# Proto_FeatherWing.net
KiCad netlist of a schematic drawn in EAGLE
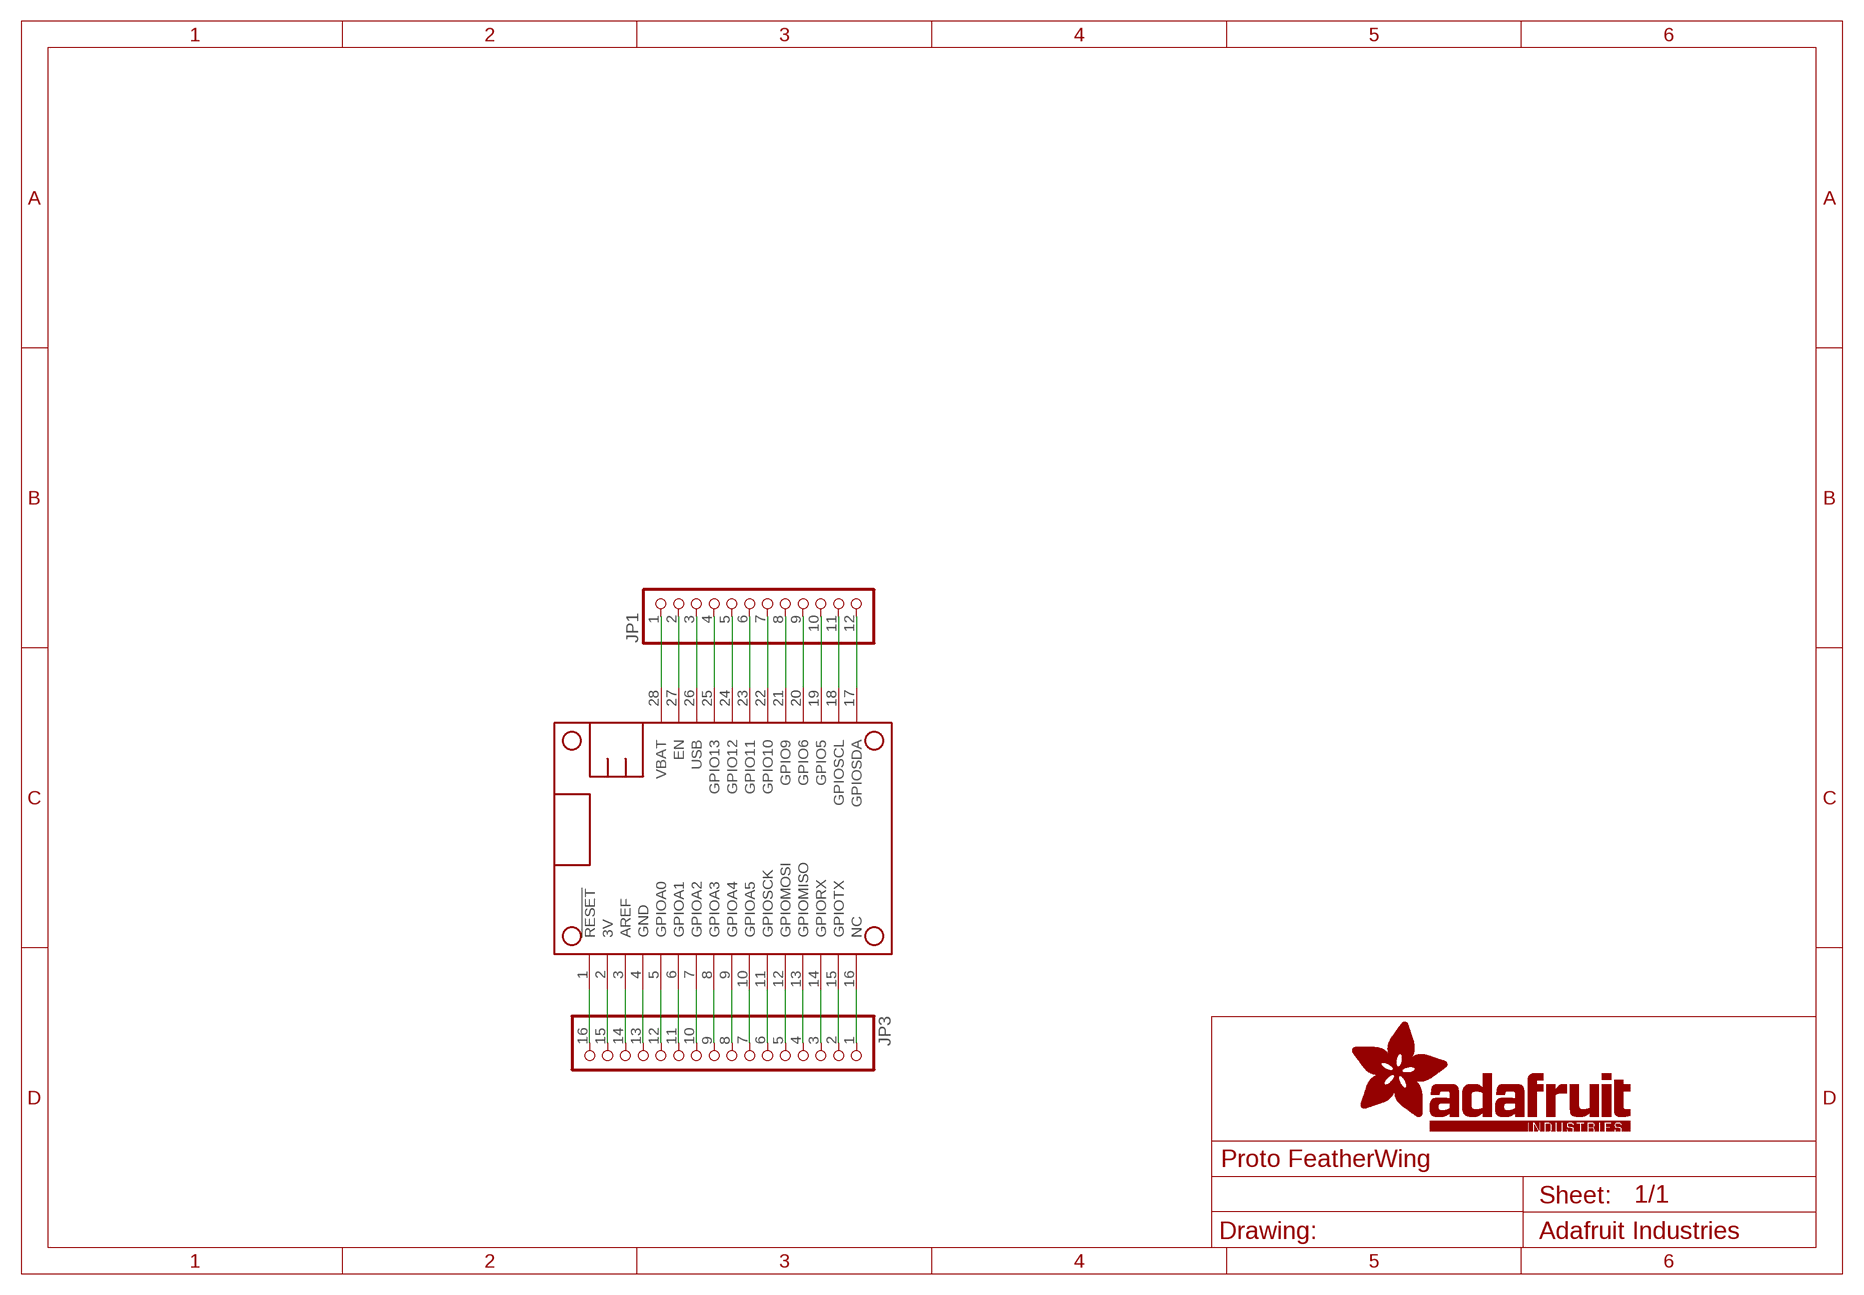
[diagram p0: schematic, sheet 1]

(export (version "E")
  (design (tool "Eeschema 10.0.6"))
  (components
    (comp (ref "JP1")
      (value "HEADER-1X1276MIL")
      (footprint "eagle-import:1X12_ROUND_76MIL")
      (libsource (lib "eagle-import") (part "HEADER-1X1276MIL"))
    )
    (comp (ref "JP3")
      (value "HEADER-1X16_76MIL")
      (footprint "eagle-import:1X16_ROUND_76MIL")
      (libsource (lib "eagle-import") (part "HEADER-1X16_76MIL"))
    )
    (comp (ref "MS1")
      (value "FEATHERWING")
      (footprint "eagle-import:FEATHERWING")
      (libsource (lib "eagle-import") (part "FEATHERWING"))
    )
  )
  (nets
    (net (code "1") (name "Net-(MS1-3V)") (class "Default")
      (node (ref "JP3") (pin "15") (pinfunction "15_15") (pintype "passive"))
      (node (ref "MS1") (pin "2") (pinfunction "3V_2") (pintype "power_in"))
    )
    (net (code "2") (name "Net-(MS1-AREF)") (class "Default")
      (node (ref "JP3") (pin "14") (pinfunction "14_14") (pintype "passive"))
      (node (ref "MS1") (pin "3") (pinfunction "AREF_3") (pintype "passive"))
    )
    (net (code "3") (name "Net-(MS1-EN)") (class "Default")
      (node (ref "JP1") (pin "2") (pinfunction "2_2") (pintype "passive"))
      (node (ref "MS1") (pin "27") (pinfunction "EN_27") (pintype "passive"))
    )
    (net (code "4") (name "Net-(MS1-GND)") (class "Default")
      (node (ref "JP3") (pin "13") (pinfunction "13_13") (pintype "passive"))
      (node (ref "MS1") (pin "4") (pinfunction "GND_4") (pintype "power_in"))
    )
    (net (code "5") (name "Net-(MS1-GPIO5)") (class "Default")
      (node (ref "JP1") (pin "10") (pinfunction "10_10") (pintype "passive"))
      (node (ref "MS1") (pin "19") (pinfunction "GPIO5_19") (pintype "bidirectional"))
    )
    (net (code "6") (name "Net-(MS1-GPIO6)") (class "Default")
      (node (ref "JP1") (pin "9") (pinfunction "9_9") (pintype "passive"))
      (node (ref "MS1") (pin "20") (pinfunction "GPIO6_20") (pintype "bidirectional"))
    )
    (net (code "7") (name "Net-(MS1-GPIO9)") (class "Default")
      (node (ref "JP1") (pin "8") (pinfunction "8_8") (pintype "passive"))
      (node (ref "MS1") (pin "21") (pinfunction "GPIO9_21") (pintype "bidirectional"))
    )
    (net (code "8") (name "Net-(MS1-GPIO10)") (class "Default")
      (node (ref "JP1") (pin "7") (pinfunction "7_7") (pintype "passive"))
      (node (ref "MS1") (pin "22") (pinfunction "GPIO10_22") (pintype "bidirectional"))
    )
    (net (code "9") (name "Net-(MS1-GPIO11)") (class "Default")
      (node (ref "JP1") (pin "6") (pinfunction "6_6") (pintype "passive"))
      (node (ref "MS1") (pin "23") (pinfunction "GPIO11_23") (pintype "bidirectional"))
    )
    (net (code "10") (name "Net-(MS1-GPIO12)") (class "Default")
      (node (ref "JP1") (pin "5") (pinfunction "5_5") (pintype "passive"))
      (node (ref "MS1") (pin "24") (pinfunction "GPIO12_24") (pintype "bidirectional"))
    )
    (net (code "11") (name "Net-(MS1-GPIO13)") (class "Default")
      (node (ref "JP1") (pin "4") (pinfunction "4_4") (pintype "passive"))
      (node (ref "MS1") (pin "25") (pinfunction "GPIO13_25") (pintype "bidirectional"))
    )
    (net (code "12") (name "Net-(MS1-GPIOA0)") (class "Default")
      (node (ref "JP3") (pin "12") (pinfunction "12_12") (pintype "passive"))
      (node (ref "MS1") (pin "5") (pinfunction "GPIOA0_5") (pintype "bidirectional"))
    )
    (net (code "13") (name "Net-(MS1-GPIOA1)") (class "Default")
      (node (ref "JP3") (pin "11") (pinfunction "11_11") (pintype "passive"))
      (node (ref "MS1") (pin "6") (pinfunction "GPIOA1_6") (pintype "bidirectional"))
    )
    (net (code "14") (name "Net-(MS1-GPIOA2)") (class "Default")
      (node (ref "JP3") (pin "10") (pinfunction "10_10") (pintype "passive"))
      (node (ref "MS1") (pin "7") (pinfunction "GPIOA2_7") (pintype "bidirectional"))
    )
    (net (code "15") (name "Net-(MS1-GPIOA3)") (class "Default")
      (node (ref "JP3") (pin "9") (pinfunction "9_9") (pintype "passive"))
      (node (ref "MS1") (pin "8") (pinfunction "GPIOA3_8") (pintype "bidirectional"))
    )
    (net (code "16") (name "Net-(MS1-GPIOA4)") (class "Default")
      (node (ref "JP3") (pin "8") (pinfunction "8_8") (pintype "passive"))
      (node (ref "MS1") (pin "9") (pinfunction "GPIOA4_9") (pintype "bidirectional"))
    )
    (net (code "17") (name "Net-(MS1-GPIOA5)") (class "Default")
      (node (ref "JP3") (pin "7") (pinfunction "7_7") (pintype "passive"))
      (node (ref "MS1") (pin "10") (pinfunction "GPIOA5_10") (pintype "bidirectional"))
    )
    (net (code "18") (name "Net-(MS1-GPIOMISO)") (class "Default")
      (node (ref "JP3") (pin "4") (pinfunction "4_4") (pintype "passive"))
      (node (ref "MS1") (pin "13") (pinfunction "GPIOMISO_13") (pintype "bidirectional"))
    )
    (net (code "19") (name "Net-(MS1-GPIOMOSI)") (class "Default")
      (node (ref "JP3") (pin "5") (pinfunction "5_5") (pintype "passive"))
      (node (ref "MS1") (pin "12") (pinfunction "GPIOMOSI_12") (pintype "bidirectional"))
    )
    (net (code "20") (name "Net-(MS1-GPIORX)") (class "Default")
      (node (ref "JP3") (pin "3") (pinfunction "3_3") (pintype "passive"))
      (node (ref "MS1") (pin "14") (pinfunction "GPIORX_14") (pintype "bidirectional"))
    )
    (net (code "21") (name "Net-(MS1-GPIOSCK)") (class "Default")
      (node (ref "JP3") (pin "6") (pinfunction "6_6") (pintype "passive"))
      (node (ref "MS1") (pin "11") (pinfunction "GPIOSCK_11") (pintype "bidirectional"))
    )
    (net (code "22") (name "Net-(MS1-GPIOSCL)") (class "Default")
      (node (ref "JP1") (pin "11") (pinfunction "11_11") (pintype "passive"))
      (node (ref "MS1") (pin "18") (pinfunction "GPIOSCL_18") (pintype "bidirectional"))
    )
    (net (code "23") (name "Net-(MS1-GPIOSDA)") (class "Default")
      (node (ref "JP1") (pin "12") (pinfunction "12_12") (pintype "passive"))
      (node (ref "MS1") (pin "17") (pinfunction "GPIOSDA_17") (pintype "bidirectional"))
    )
    (net (code "24") (name "Net-(MS1-GPIOTX)") (class "Default")
      (node (ref "JP3") (pin "2") (pinfunction "2_2") (pintype "passive"))
      (node (ref "MS1") (pin "15") (pinfunction "GPIOTX_15") (pintype "bidirectional"))
    )
    (net (code "25") (name "Net-(MS1-NC)") (class "Default")
      (node (ref "JP3") (pin "1") (pinfunction "1_1") (pintype "passive"))
      (node (ref "MS1") (pin "16") (pinfunction "NC_16") (pintype "passive"))
    )
    (net (code "26") (name "Net-(MS1-USB)") (class "Default")
      (node (ref "JP1") (pin "3") (pinfunction "3_3") (pintype "passive"))
      (node (ref "MS1") (pin "26") (pinfunction "USB_26") (pintype "power_in"))
    )
    (net (code "27") (name "Net-(MS1-VBAT)") (class "Default")
      (node (ref "JP1") (pin "1") (pinfunction "1_1") (pintype "passive"))
      (node (ref "MS1") (pin "28") (pinfunction "VBAT_28") (pintype "power_in"))
    )
    (net (code "28") (name "Net-(MS1-~{RESET})") (class "Default")
      (node (ref "JP3") (pin "16") (pinfunction "16_16") (pintype "passive"))
      (node (ref "MS1") (pin "1") (pinfunction "~{RESET}_1") (pintype "input"))
    )
  )
)
